# BIN.net
KiCad netlist of a schematic drawn in Altium Designer
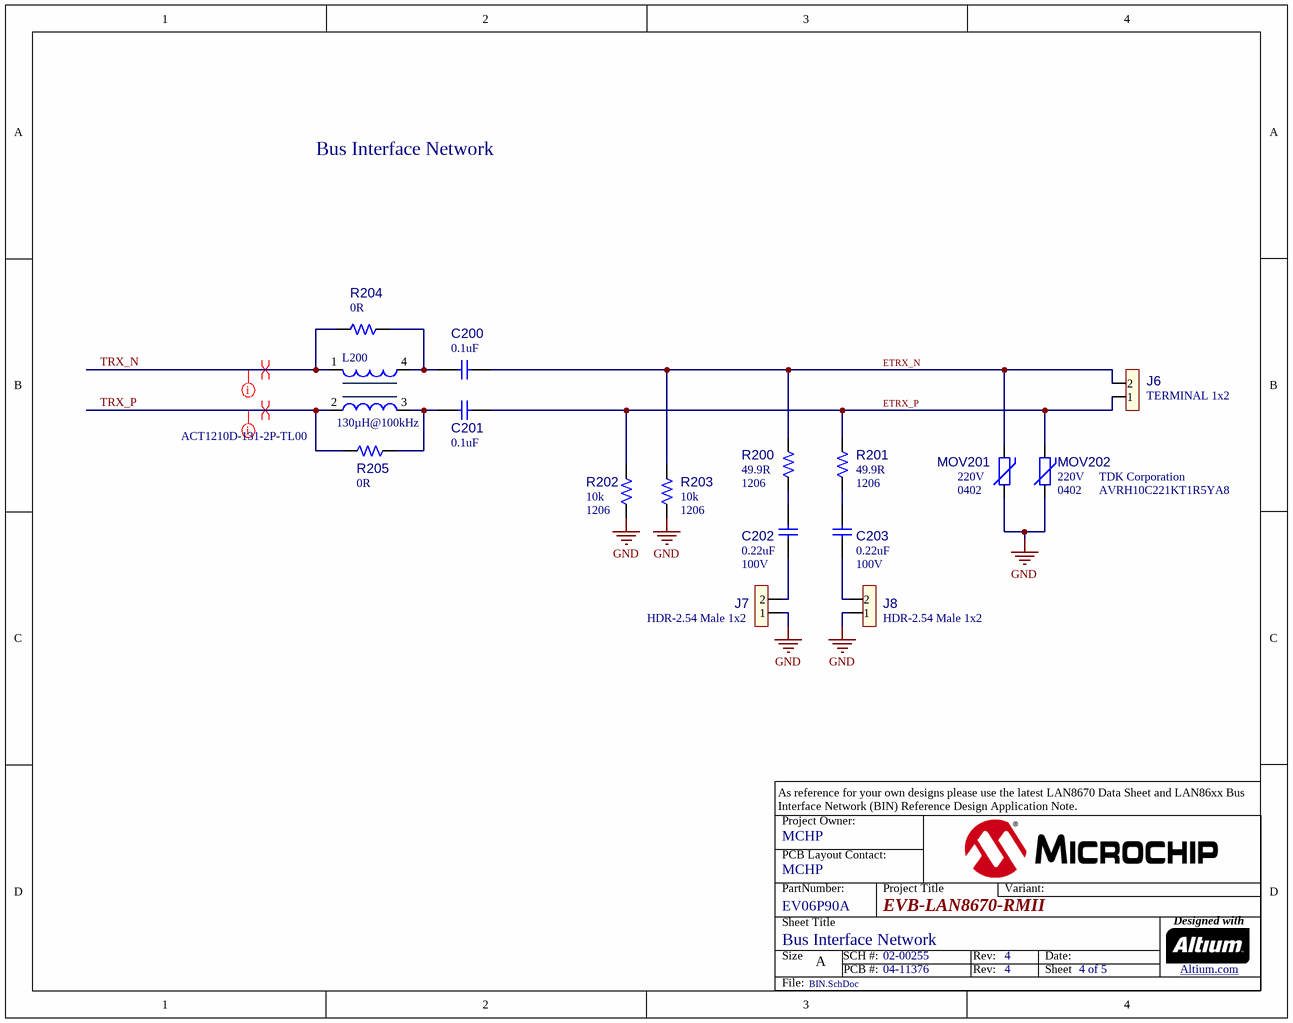
[diagram p0: BIN.SchDoc]

(export (version "E")
  (design (tool "Eeschema 10.0.6"))
  (components
    (comp (ref "C200")
      (value "0.1uF")
      (footprint "CAP_C_0402")
      (fields
        (field (name "VOLTAGE") "50V")
        (field (name "TOLERANCE") "10%")
        (field (name "Comment") "Capacitor NP")
        (field (name "OWNER") "Dragos Danaila")
      )
      (libsource (lib "MCL-Offline") (part "Capacitor NP"))
    )
    (comp (ref "C201")
      (value "0.1uF")
      (footprint "CAP_C_0402")
      (fields
        (field (name "VOLTAGE") "50V")
        (field (name "TOLERANCE") "10%")
        (field (name "Comment") "Capacitor NP")
        (field (name "OWNER") "Dragos Danaila")
      )
      (libsource (lib "MCL-Offline") (part "Capacitor NP"))
    )
    (comp (ref "C202")
      (value "0.22uF")
      (footprint "CAP_C_0805")
      (fields
        (field (name "VOLTAGE") "100V")
        (field (name "TOLERANCE") "±10%")
        (field (name "Comment") "Capacitor NP")
        (field (name "OWNER") "Lori Graham")
      )
      (libsource (lib "MCL-Offline") (part "Capacitor NP"))
    )
    (comp (ref "C203")
      (value "0.22uF")
      (footprint "CAP_C_0805")
      (fields
        (field (name "VOLTAGE") "100V")
        (field (name "TOLERANCE") "±10%")
        (field (name "Comment") "Capacitor NP")
        (field (name "OWNER") "Lori Graham")
      )
      (libsource (lib "MCL-Offline") (part "Capacitor NP"))
    )
    (comp (ref "J6")
      (value "TERMINAL 1x2")
      (footprint "CON_TB_3.5mm_2POS_WE_WR-TBL-691214110002S")
      (fields
        (field (name "VOLTAGE") "300V")
        (field (name "Comment") "Header 1x2")
        (field (name "OWNER") "Lori Graham")
      )
      (libsource (lib "MCL-Offline") (part "Header 1x2"))
    )
    (comp (ref "J7")
      (value "HDR-2.54 Male 1x2")
      (footprint "HDR_M_2.54_1x2")
      (fields (field (name "Comment") "Header 1x2") (field (name "OWNER") "Lori Graham"))
      (libsource (lib "") (part "Header 1x2_1"))
    )
    (comp (ref "J8")
      (value "HDR-2.54 Male 1x2")
      (footprint "HDR_M_2.54_1x2")
      (fields (field (name "Comment") "Header 1x2") (field (name "OWNER") "Lori Graham"))
      (libsource (lib "MCL-Offline") (part "Header 1x2"))
    )
    (comp (ref "L200")
      (value "130µH@100kHz")
      (footprint "IND_TDK_ACT1210D_L3.9W2.5H2.5")
      (fields
        (field (name "MANUFACTURER PART NUMBER 1") "ACT1210D-131-2P-TL00")
        (field (name "Comment") "Inductor Choke ACT1210")
        (field (name "OWNER") "Joerg Buehrer")
      )
      (libsource (lib "MCL-Offline") (part "Inductor Choke ACT1210"))
    )
    (comp (ref "MOV201")
      (value "220V")
      (footprint "RES_C_0402")
      (description "Varistor")
      (fields (field (name "PACKAGE") "0402") (field (name "OWNER") "Sam Charles"))
      (libsource (lib "MCL-Offline") (part "Varistor"))
    )
    (comp (ref "MOV202")
      (value "220V")
      (footprint "RES_C_0402")
      (description "Varistor")
      (fields
        (field (name "PACKAGE") "0402")
        (field (name "MANUFACTURER 1") "TDK Corporation")
        (field (name "MANUFACTURER PART NUMBER 1") "AVRH10C221KT1R5YA8")
        (field (name "OWNER") "Sam Charles")
      )
      (libsource (lib "MCL-Offline") (part "Varistor"))
    )
    (comp (ref "R200")
      (value "49.9R")
      (footprint "RES_C_1206")
      (description "Resistor")
      (fields
        (field (name "PACKAGE") "1206")
        (field (name "VOLTAGE") "200V")
        (field (name "TOLERANCE") "±0.1%")
        (field (name "OWNER") "Lori Graham")
      )
      (libsource (lib "MCL-Offline") (part "Resistor"))
    )
    (comp (ref "R201")
      (value "49.9R")
      (footprint "RES_C_1206")
      (description "Resistor")
      (fields
        (field (name "PACKAGE") "1206")
        (field (name "VOLTAGE") "200V")
        (field (name "TOLERANCE") "±0.1%")
        (field (name "OWNER") "Lori Graham")
      )
      (libsource (lib "MCL-Offline") (part "Resistor"))
    )
    (comp (ref "R202")
      (value "10k")
      (footprint "RES_C_1206")
      (description "Resistor")
      (fields
        (field (name "TOLERANCE") "1%")
        (field (name "PACKAGE") "1206")
        (field (name "POWER") "1/4W")
        (field (name "OWNER") "Gabor Bihari")
      )
      (libsource (lib "MCHP-CDB") (part "Resistor"))
    )
    (comp (ref "R203")
      (value "10k")
      (footprint "RES_C_1206")
      (description "Resistor")
      (fields
        (field (name "TOLERANCE") "1%")
        (field (name "PACKAGE") "1206")
        (field (name "POWER") "1/4W")
        (field (name "OWNER") "Gabor Bihari")
      )
      (libsource (lib "MCHP-CDB") (part "Resistor"))
    )
    (comp (ref "R204")
      (value "0R")
      (footprint "RES_C_0402")
      (description "Resistor")
      (fields
        (field (name "TOLERANCE") "50mOhm")
        (field (name "VOLTAGE") "50V")
        (field (name "OWNER") "Dragos Danaila")
      )
      (libsource (lib "MCHP-CDB") (part "Resistor"))
    )
    (comp (ref "R205")
      (value "0R")
      (footprint "RES_C_0402")
      (description "Resistor")
      (fields
        (field (name "TOLERANCE") "50mOhm")
        (field (name "VOLTAGE") "50V")
        (field (name "OWNER") "Dragos Danaila")
      )
      (libsource (lib "MCHP-CDB") (part "Resistor"))
    )
  )
  (nets
    (net (code "1") (name "/ETRX_N") (class "Default")
      (node (ref "C200") (pin "2") (pinfunction "2_2") (pintype "passive"))
      (node (ref "J6") (pin "2") (pinfunction "2_2") (pintype "passive"))
      (node (ref "MOV201") (pin "2") (pinfunction "2_2") (pintype "passive"))
      (node (ref "R200") (pin "2") (pinfunction "2_2") (pintype "passive"))
      (node (ref "R203") (pin "1") (pinfunction "1_1") (pintype "passive"))
    )
    (net (code "2") (name "/ETRX_P") (class "Default")
      (node (ref "C201") (pin "2") (pinfunction "2_2") (pintype "passive"))
      (node (ref "J6") (pin "1") (pinfunction "1_1") (pintype "passive"))
      (node (ref "MOV202") (pin "2") (pinfunction "2_2") (pintype "passive"))
      (node (ref "R201") (pin "2") (pinfunction "2_2") (pintype "passive"))
      (node (ref "R202") (pin "1") (pinfunction "1_1") (pintype "passive"))
    )
    (net (code "3") (name "/TRX_N") (class "Default")
      (node (ref "L200") (pin "1") (pinfunction "1_1") (pintype "passive"))
      (node (ref "R204") (pin "1") (pinfunction "1_1") (pintype "passive"))
    )
    (net (code "4") (name "/TRX_P") (class "Default")
      (node (ref "L200") (pin "2") (pinfunction "2_2") (pintype "passive"))
      (node (ref "R205") (pin "1") (pinfunction "1_1") (pintype "passive"))
    )
    (net (code "5") (name "GND") (class "Default")
      (node (ref "J7") (pin "1") (pinfunction "1_1") (pintype "passive"))
      (node (ref "J8") (pin "1") (pinfunction "1_1") (pintype "passive"))
      (node (ref "MOV201") (pin "1") (pinfunction "1_1") (pintype "passive"))
      (node (ref "MOV202") (pin "1") (pinfunction "1_1") (pintype "passive"))
      (node (ref "R202") (pin "2") (pinfunction "2_2") (pintype "passive"))
      (node (ref "R203") (pin "2") (pinfunction "2_2") (pintype "passive"))
    )
    (net (code "6") (name "Net-(C200-Pad1)") (class "Default")
      (node (ref "C200") (pin "1") (pinfunction "1_1") (pintype "passive"))
      (node (ref "L200") (pin "4") (pinfunction "4_4") (pintype "passive"))
      (node (ref "R204") (pin "2") (pinfunction "2_2") (pintype "passive"))
    )
    (net (code "7") (name "Net-(C201-Pad1)") (class "Default")
      (node (ref "C201") (pin "1") (pinfunction "1_1") (pintype "passive"))
      (node (ref "L200") (pin "3") (pinfunction "3_3") (pintype "passive"))
      (node (ref "R205") (pin "2") (pinfunction "2_2") (pintype "passive"))
    )
    (net (code "8") (name "Net-(C202-Pad1)") (class "Default")
      (node (ref "C202") (pin "1") (pinfunction "1_1") (pintype "passive"))
      (node (ref "J7") (pin "2") (pinfunction "2_2") (pintype "passive"))
    )
    (net (code "9") (name "Net-(C202-Pad2)") (class "Default")
      (node (ref "C202") (pin "2") (pinfunction "2_2") (pintype "passive"))
      (node (ref "R200") (pin "1") (pinfunction "1_1") (pintype "passive"))
    )
    (net (code "10") (name "Net-(C203-Pad1)") (class "Default")
      (node (ref "C203") (pin "1") (pinfunction "1_1") (pintype "passive"))
      (node (ref "J8") (pin "2") (pinfunction "2_2") (pintype "passive"))
    )
    (net (code "11") (name "Net-(C203-Pad2)") (class "Default")
      (node (ref "C203") (pin "2") (pinfunction "2_2") (pintype "passive"))
      (node (ref "R201") (pin "1") (pinfunction "1_1") (pintype "passive"))
    )
  )
)
